# 01_Power.net
KiCad netlist of a schematic drawn in Altium Designer
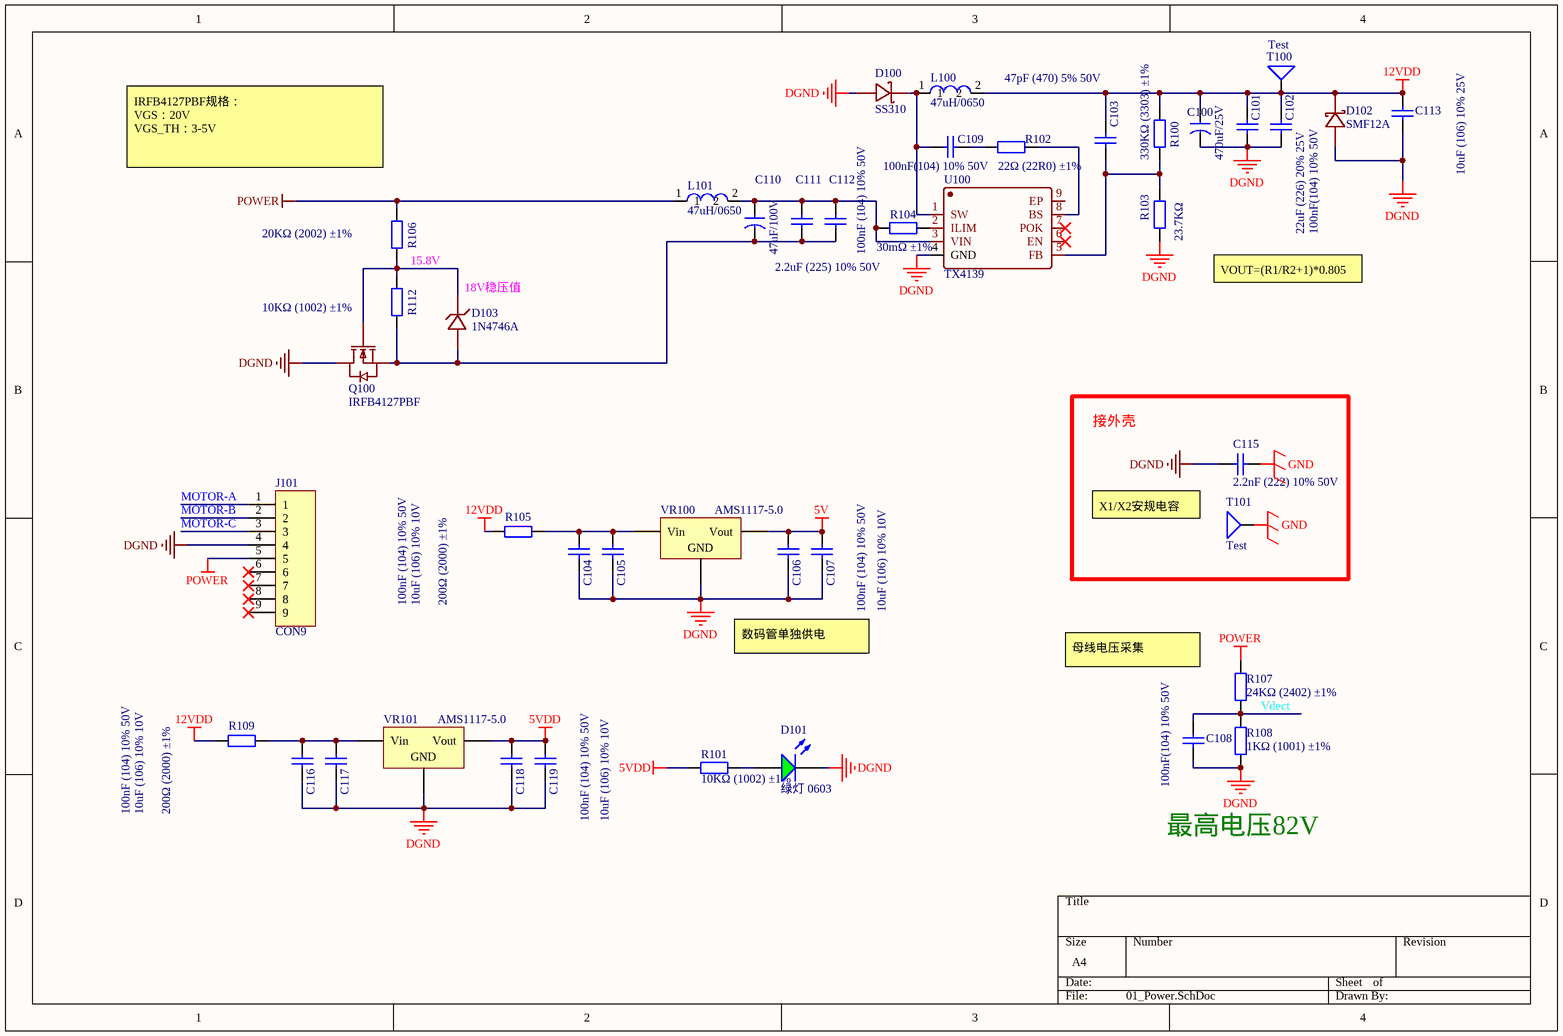
[diagram p0: 01_Power.SchDoc]

(export (version "E")
  (design (tool "Eeschema 10.0.6"))
  (components
    (comp (ref "C100")
      (value "470uF/25V")
      (footprint "47UF/100V")
      (libsource (lib "RayPCB20210502") (part "CapSMT220u_16V"))
    )
    (comp (ref "C101")
      (value "22uF (226) 20% 25V")
      (footprint "0805_C")
      (description "贴片电容")
      (libsource (lib "Miscellaneous Devices LC") (part "0805 22uF (226) 20% 25V"))
    )
    (comp (ref "C102")
      (value "100nF(104) 10% 50V")
      (footprint "0805_C")
      (description "贴片电容")
      (libsource (lib "Miscellaneous Devices LC") (part "0805 100nF(104) 10% 50V"))
    )
    (comp (ref "C103")
      (value "47pF (470) 5% 50V")
      (footprint "0805_C")
      (description "贴片电容")
      (libsource (lib "Miscellaneous Devices LC") (part "0805 47pF (470) 5% 50V"))
    )
    (comp (ref "C104")
      (value "100nF (104) 10% 50V")
      (footprint "0603_C")
      (description "贴片电容")
      (libsource (lib "Miscellaneous Devices LC") (part "0603 100nF (104) 10% 50V"))
    )
    (comp (ref "C105")
      (value "10uF (106) 10% 10V")
      (footprint "0603_C")
      (description "贴片电容")
      (libsource (lib "Miscellaneous Devices LC") (part "0603 10uF (106) 10% 10V"))
    )
    (comp (ref "C106")
      (value "100nF (104) 10% 50V")
      (footprint "0603_C")
      (description "贴片电容")
      (libsource (lib "Miscellaneous Devices LC") (part "0603 100nF (104) 10% 50V"))
    )
    (comp (ref "C107")
      (value "10uF (106) 10% 10V")
      (footprint "0603_C")
      (description "贴片电容")
      (libsource (lib "Miscellaneous Devices LC") (part "0603 10uF (106) 10% 10V"))
    )
    (comp (ref "C108")
      (value "100nF(104) 10% 50V")
      (footprint "0805_C")
      (description "贴片电容")
      (libsource (lib "Miscellaneous Devices LC") (part "0805 100nF(104) 10% 50V"))
    )
    (comp (ref "C109")
      (value "100nF(104) 10% 50V")
      (footprint "0805_C")
      (description "贴片电容")
      (libsource (lib "Miscellaneous Devices LC") (part "0805 100nF(104) 10% 50V"))
    )
    (comp (ref "C110")
      (value "47uF/100V")
      (footprint "47UF/100V")
      (libsource (lib "RayPCB20210502") (part "CapSMT220u_16V"))
    )
    (comp (ref "C111")
      (value "2.2uF (225) 10% 50V")
      (footprint "1206_C")
      (description "贴片电容")
      (libsource (lib "Miscellaneous Devices LC") (part "1206 2.2uF (225) 10% 50V"))
    )
    (comp (ref "C112")
      (value "100nF (104) 10% 50V")
      (footprint "1206_C")
      (description "贴片电容")
      (libsource (lib "Miscellaneous Devices LC") (part "1206 100nF (104) 10% 50V"))
    )
    (comp (ref "C113")
      (value "10uF (106) 10% 25V")
      (footprint "0805_C")
      (description "贴片电容")
      (libsource (lib "Miscellaneous Devices LC") (part "0805 10uF (106) 10% 25V"))
    )
    (comp (ref "C115")
      (value "2.2nF (222) 10% 50V")
      (footprint "X1/Y1 500V")
      (description "贴片电容")
      (libsource (lib "Miscellaneous Devices LC") (part "0603 2.2nF (222) 10% 50V"))
    )
    (comp (ref "C116")
      (value "100nF (104) 10% 50V")
      (footprint "0603_C")
      (description "贴片电容")
      (libsource (lib "Miscellaneous Devices LC") (part "0603 100nF (104) 10% 50V"))
    )
    (comp (ref "C117")
      (value "10uF (106) 10% 10V")
      (footprint "0603_C")
      (description "贴片电容")
      (libsource (lib "Miscellaneous Devices LC") (part "0603 10uF (106) 10% 10V"))
    )
    (comp (ref "C118")
      (value "100nF (104) 10% 50V")
      (footprint "0603_C")
      (description "贴片电容")
      (libsource (lib "Miscellaneous Devices LC") (part "0603 100nF (104) 10% 50V"))
    )
    (comp (ref "C119")
      (value "10uF (106) 10% 10V")
      (footprint "0603_C")
      (description "贴片电容")
      (libsource (lib "Miscellaneous Devices LC") (part "0603 10uF (106) 10% 10V"))
    )
    (comp (ref "D100") (value "SS310") (footprint "SS310") (libsource (lib "Schlibv2") (part "SS310")))
    (comp (ref "D101")
      (value "绿灯 0603")
      (footprint "0603_LED_S1")
      (description "发光二极管")
      (libsource (lib "Miscellaneous Devices LC") (part "0603 绿灯"))
    )
    (comp (ref "D102")
      (value "SMF12A")
      (footprint "SMF12A - duplicate")
      (libsource (lib "RayPCB20210502") (part "SMF12A"))
    )
    (comp (ref "D103") (value "1N4746A") (footprint "1N4746A") (libsource (lib "Schlibv2") (part "1N4746A")))
    (comp (ref "J101")
      (value "CON9")
      (footprint "CON9 9.5mm")
      (libsource (lib "RayPCB20210502") (part "CON9"))
    )
    (comp (ref "L100")
      (value "47uH/0650")
      (footprint "0650_47uH")
      (libsource (lib "RayPCB20210502") (part "Inductor"))
    )
    (comp (ref "L101")
      (value "47uH/0650")
      (footprint "0650_47uH")
      (libsource (lib "RayPCB20210502") (part "Inductor"))
    )
    (comp (ref "Q100")
      (value "IRFB4127PBF")
      (footprint "IRFB4127")
      (libsource (lib "RayPCB20210502") (part "IRFB4127PBF"))
    )
    (comp (ref "R100")
      (value "330KΩ (3303) ±1%")
      (footprint "0805_R")
      (description "贴片电阻")
      (libsource (lib "Miscellaneous Devices LC") (part "0805 330KΩ (3303) 1%"))
    )
    (comp (ref "R101")
      (value "10KΩ (1002) ±1%")
      (footprint "0603_R")
      (description "贴片电阻")
      (libsource (lib "Miscellaneous Devices LC") (part "0603 10KΩ (1002) 1%"))
    )
    (comp (ref "R102")
      (value "22Ω (22R0) ±1%")
      (footprint "0805_R")
      (description "贴片电阻")
      (libsource (lib "Miscellaneous Devices LC") (part "0805 22Ω (22R0) 1%"))
    )
    (comp (ref "R103")
      (value "23.7KΩ")
      (footprint "0805_R")
      (description "贴片电阻")
      (libsource (lib "") (part "0805 22Ω (22R0) 1%_1"))
    )
    (comp (ref "R104")
      (value "30mΩ ±1%")
      (footprint "0603_R")
      (description "贴片电阻")
      (libsource (lib "Miscellaneous Devices LC") (part "0603 100KΩ (1003) 1%"))
    )
    (comp (ref "R105")
      (value "200Ω (2000) ±1%")
      (footprint "1206_R")
      (description "贴片电阻")
      (libsource (lib "Miscellaneous Devices LC") (part "1206 300Ω (3000) 1%"))
    )
    (comp (ref "R106")
      (value "20KΩ (2002) ±1%")
      (footprint "0805_R")
      (description "贴片电阻")
      (libsource (lib "Miscellaneous Devices LC") (part "0805 20KΩ (2002) 1%"))
    )
    (comp (ref "R107")
      (value "24KΩ (2402) ±1%")
      (footprint "1206_R")
      (description "贴片电阻")
      (libsource (lib "Miscellaneous Devices LC") (part "1206 0Ω (0R0) 1%"))
    )
    (comp (ref "R108")
      (value "1KΩ (1001) ±1%")
      (footprint "0805_R")
      (description "贴片电阻")
      (libsource (lib "Miscellaneous Devices LC") (part "0805 1KΩ (1001) 1%"))
    )
    (comp (ref "R109")
      (value "200Ω (2000) ±1%")
      (footprint "1206_R")
      (description "贴片电阻")
      (libsource (lib "Miscellaneous Devices LC") (part "1206 300Ω (3000) 1%"))
    )
    (comp (ref "R112")
      (value "10KΩ (1002) ±1%")
      (footprint "0805_R")
      (description "贴片电阻")
      (libsource (lib "Miscellaneous Devices LC") (part "0805 10KΩ (1002) 1%"))
    )
    (comp (ref "T100")
      (value "Test")
      (footprint "Testpoint")
      (libsource (lib "RayPCB20210502") (part "TestPad"))
    )
    (comp (ref "T101") (value "Test") (footprint "接地螺丝孔") (libsource (lib "RayPCB20210502") (part "TestPad")))
    (comp (ref "U100")
      (value "TX4139")
      (footprint "ESOP8")
      (libsource (lib "RayPCB20210502") (part "TX4139"))
    )
    (comp (ref "VR100")
      (value "AMS1117-5.0")
      (footprint "SOT-223")
      (description "低压差线性稳压(LDO)")
      (libsource (lib "Miscellaneous Devices LC") (part "SOT-223 AMS1117-5.0"))
    )
    (comp (ref "VR101")
      (value "AMS1117-5.0")
      (footprint "SOT-223")
      (description "低压差线性稳压(LDO)")
      (libsource (lib "Miscellaneous Devices LC") (part "SOT-223 AMS1117-5.0"))
    )
  )
  (nets
    (net (code "1") (name "/MOTOR-A") (class "Default")
      (node (ref "J101") (pin "1") (pinfunction "1_1") (pintype "passive"))
    )
    (net (code "2") (name "/MOTOR-B") (class "Default")
      (node (ref "J101") (pin "2") (pinfunction "2_2") (pintype "passive"))
    )
    (net (code "3") (name "/MOTOR-C") (class "Default")
      (node (ref "J101") (pin "3") (pinfunction "3_3") (pintype "passive"))
    )
    (net (code "4") (name "/Vdect") (class "Default")
      (node (ref "C108") (pin "2") (pinfunction "2_2") (pintype "passive"))
      (node (ref "R107") (pin "1") (pinfunction "1_1") (pintype "passive"))
      (node (ref "R108") (pin "2") (pinfunction "2_2") (pintype "passive"))
    )
    (net (code "5") (name "5V") (class "Default")
      (node (ref "C106") (pin "2") (pinfunction "2_2") (pintype "passive"))
      (node (ref "C107") (pin "2") (pinfunction "2_2") (pintype "passive"))
      (node (ref "VR100") (pin "2") (pinfunction "Vout_2") (pintype "passive"))
    )
    (net (code "6") (name "5VDD") (class "Default")
      (node (ref "C118") (pin "2") (pinfunction "2_2") (pintype "passive"))
      (node (ref "C119") (pin "2") (pinfunction "2_2") (pintype "passive"))
      (node (ref "R101") (pin "2") (pinfunction "2_2") (pintype "passive"))
      (node (ref "VR101") (pin "2") (pinfunction "Vout_2") (pintype "passive"))
    )
    (net (code "7") (name "12VDD") (class "Default")
      (node (ref "C100") (pin "1") (pintype "passive"))
      (node (ref "C101") (pin "2") (pinfunction "2_2") (pintype "passive"))
      (node (ref "C102") (pin "2") (pinfunction "2_2") (pintype "passive"))
      (node (ref "C103") (pin "2") (pinfunction "2_2") (pintype "passive"))
      (node (ref "C113") (pin "1") (pinfunction "1_1") (pintype "passive"))
      (node (ref "D102") (pin "1") (pinfunction "K_1") (pintype "passive"))
      (node (ref "L100") (pin "2") (pinfunction "2_2") (pintype "passive"))
      (node (ref "R100") (pin "2") (pinfunction "2_2") (pintype "passive"))
      (node (ref "R105") (pin "1") (pinfunction "1_1") (pintype "passive"))
      (node (ref "R109") (pin "1") (pinfunction "1_1") (pintype "passive"))
      (node (ref "T100") (pin "1") (pinfunction "1_1") (pintype "passive"))
    )
    (net (code "8") (name "DGND") (class "Default")
      (node (ref "C100") (pin "2") (pintype "passive"))
      (node (ref "C101") (pin "1") (pinfunction "1_1") (pintype "passive"))
      (node (ref "C102") (pin "1") (pinfunction "1_1") (pintype "passive"))
      (node (ref "C104") (pin "1") (pinfunction "1_1") (pintype "passive"))
      (node (ref "C105") (pin "1") (pinfunction "1_1") (pintype "passive"))
      (node (ref "C106") (pin "1") (pinfunction "1_1") (pintype "passive"))
      (node (ref "C107") (pin "1") (pinfunction "1_1") (pintype "passive"))
      (node (ref "C108") (pin "1") (pinfunction "1_1") (pintype "passive"))
      (node (ref "C113") (pin "2") (pinfunction "2_2") (pintype "passive"))
      (node (ref "C115") (pin "1") (pinfunction "1_1") (pintype "passive"))
      (node (ref "C116") (pin "1") (pinfunction "1_1") (pintype "passive"))
      (node (ref "C117") (pin "1") (pinfunction "1_1") (pintype "passive"))
      (node (ref "C118") (pin "1") (pinfunction "1_1") (pintype "passive"))
      (node (ref "C119") (pin "1") (pinfunction "1_1") (pintype "passive"))
      (node (ref "D100") (pin "2") (pinfunction "A_2") (pintype "passive"))
      (node (ref "D101") (pin "K") (pinfunction "K_K") (pintype "passive"))
      (node (ref "D102") (pin "2") (pinfunction "A_2") (pintype "passive"))
      (node (ref "J101") (pin "4") (pinfunction "4_4") (pintype "passive"))
      (node (ref "Q100") (pin "2") (pinfunction "D_2") (pintype "passive"))
      (node (ref "R103") (pin "1") (pinfunction "1_1") (pintype "passive"))
      (node (ref "R108") (pin "1") (pinfunction "1_1") (pintype "passive"))
      (node (ref "U100") (pin "4") (pinfunction "GND_4") (pintype "passive"))
      (node (ref "VR100") (pin "1") (pinfunction "GND_1") (pintype "passive"))
      (node (ref "VR101") (pin "1") (pinfunction "GND_1") (pintype "passive"))
    )
    (net (code "9") (name "GND") (class "Default")
      (node (ref "C115") (pin "2") (pinfunction "2_2") (pintype "passive"))
      (node (ref "T101") (pin "1") (pinfunction "1_1") (pintype "passive"))
    )
    (net (code "10") (name "Net-(C109-Pad2)") (class "Default")
      (node (ref "C109") (pin "2") (pinfunction "2_2") (pintype "passive"))
      (node (ref "R102") (pin "1") (pinfunction "1_1") (pintype "passive"))
    )
    (net (code "11") (name "Net-(D100-K)") (class "Default")
      (node (ref "C109") (pin "1") (pinfunction "1_1") (pintype "passive"))
      (node (ref "D100") (pin "1") (pinfunction "K_1") (pintype "passive"))
      (node (ref "L100") (pin "1") (pinfunction "1_1") (pintype "passive"))
      (node (ref "U100") (pin "1") (pinfunction "SW_1") (pintype "passive"))
    )
    (net (code "12") (name "Net-(D101-PadA)") (class "Default")
      (node (ref "D101") (pin "A") (pinfunction "A_A") (pintype "passive"))
      (node (ref "R101") (pin "1") (pinfunction "1_1") (pintype "passive"))
    )
    (net (code "13") (name "Net-(D103-A)") (class "Default")
      (node (ref "C110") (pin "2") (pintype "passive"))
      (node (ref "C111") (pin "1") (pinfunction "1_1") (pintype "passive"))
      (node (ref "C112") (pin "1") (pinfunction "1_1") (pintype "passive"))
      (node (ref "D103") (pin "1") (pinfunction "A_1") (pintype "passive"))
      (node (ref "Q100") (pin "3") (pinfunction "S_3") (pintype "passive"))
      (node (ref "R112") (pin "1") (pinfunction "1_1") (pintype "passive"))
    )
    (net (code "14") (name "Net-(D103-K)") (class "Default")
      (node (ref "D103") (pin "2") (pinfunction "K_2") (pintype "passive"))
      (node (ref "Q100") (pin "1") (pinfunction "G_1") (pintype "passive"))
      (node (ref "R106") (pin "1") (pinfunction "1_1") (pintype "passive"))
      (node (ref "R112") (pin "2") (pinfunction "2_2") (pintype "passive"))
    )
    (net (code "15") (name "Net-(U100-BS)") (class "Default")
      (node (ref "R102") (pin "2") (pinfunction "2_2") (pintype "passive"))
      (node (ref "U100") (pin "8") (pinfunction "BS_8") (pintype "passive"))
    )
    (net (code "16") (name "Net-(U100-FB)") (class "Default")
      (node (ref "C103") (pin "1") (pinfunction "1_1") (pintype "passive"))
      (node (ref "R100") (pin "1") (pinfunction "1_1") (pintype "passive"))
      (node (ref "R103") (pin "2") (pinfunction "2_2") (pintype "passive"))
      (node (ref "U100") (pin "5") (pinfunction "FB_5") (pintype "passive"))
    )
    (net (code "17") (name "Net-(U100-ILIM)") (class "Default")
      (node (ref "R104") (pin "1") (pinfunction "1_1") (pintype "passive"))
      (node (ref "U100") (pin "2") (pinfunction "ILIM_2") (pintype "passive"))
    )
    (net (code "18") (name "Net-(U100-VIN)") (class "Default")
      (node (ref "C110") (pin "1") (pintype "passive"))
      (node (ref "C111") (pin "2") (pinfunction "2_2") (pintype "passive"))
      (node (ref "C112") (pin "2") (pinfunction "2_2") (pintype "passive"))
      (node (ref "L101") (pin "2") (pinfunction "2_2") (pintype "passive"))
      (node (ref "R104") (pin "2") (pinfunction "2_2") (pintype "passive"))
      (node (ref "U100") (pin "3") (pinfunction "VIN_3") (pintype "passive"))
    )
    (net (code "19") (name "Net-(VR100-Vin)") (class "Default")
      (node (ref "C104") (pin "2") (pinfunction "2_2") (pintype "passive"))
      (node (ref "C105") (pin "2") (pinfunction "2_2") (pintype "passive"))
      (node (ref "R105") (pin "2") (pinfunction "2_2") (pintype "passive"))
      (node (ref "VR100") (pin "3") (pinfunction "Vin_3") (pintype "passive"))
    )
    (net (code "20") (name "Net-(VR101-Vin)") (class "Default")
      (node (ref "C116") (pin "2") (pinfunction "2_2") (pintype "passive"))
      (node (ref "C117") (pin "2") (pinfunction "2_2") (pintype "passive"))
      (node (ref "R109") (pin "2") (pinfunction "2_2") (pintype "passive"))
      (node (ref "VR101") (pin "3") (pinfunction "Vin_3") (pintype "passive"))
    )
    (net (code "21") (name "POWER") (class "Default")
      (node (ref "J101") (pin "5") (pinfunction "5_5") (pintype "passive"))
      (node (ref "L101") (pin "1") (pinfunction "1_1") (pintype "passive"))
      (node (ref "R106") (pin "2") (pinfunction "2_2") (pintype "passive"))
      (node (ref "R107") (pin "2") (pinfunction "2_2") (pintype "passive"))
    )
    (net (code "22") (name "unconnected-(J101-Pad6)") (class "Default")
      (node (ref "J101") (pin "6") (pinfunction "6_6") (pintype "passive+no_connect"))
    )
    (net (code "23") (name "unconnected-(J101-Pad7)") (class "Default")
      (node (ref "J101") (pin "7") (pinfunction "7_7") (pintype "passive+no_connect"))
    )
    (net (code "24") (name "unconnected-(J101-Pad8)") (class "Default")
      (node (ref "J101") (pin "8") (pinfunction "8_8") (pintype "passive+no_connect"))
    )
    (net (code "25") (name "unconnected-(J101-Pad9)") (class "Default")
      (node (ref "J101") (pin "9") (pinfunction "9_9") (pintype "passive+no_connect"))
    )
    (net (code "26") (name "unconnected-(U100-EN-Pad6)") (class "Default")
      (node (ref "U100") (pin "6") (pinfunction "EN_6") (pintype "passive+no_connect"))
    )
    (net (code "27") (name "unconnected-(U100-EP-Pad9)") (class "Default")
      (node (ref "U100") (pin "9") (pinfunction "EP_9") (pintype "passive"))
    )
    (net (code "28") (name "unconnected-(U100-POK-Pad7)") (class "Default")
      (node (ref "U100") (pin "7") (pinfunction "POK_7") (pintype "passive+no_connect"))
    )
  )
)
